# control_board-M0_breakout.net
KiCad netlist of a schematic drawn in EAGLE
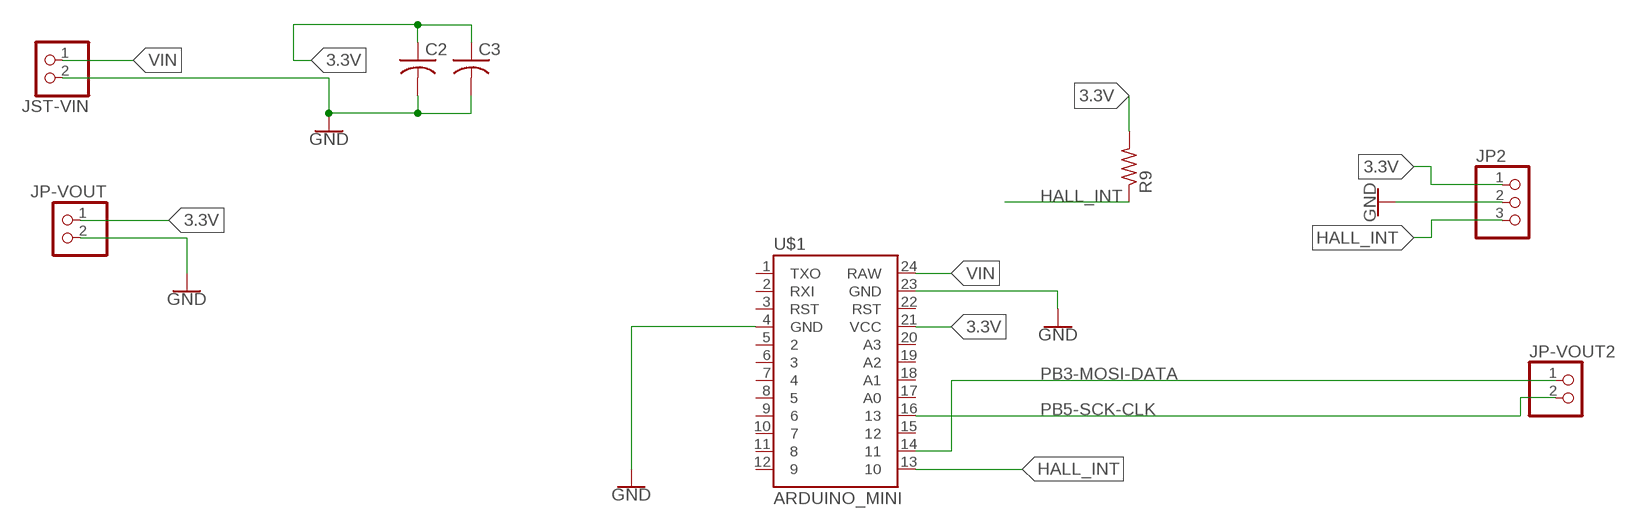
[diagram p0: schematic, sheet 1]

(export (version "E")
  (design (tool "Eeschema 10.0.6"))
  (components
    (comp (ref "C2")
      (value "C-US025-060X050")
      (footprint "eagle-import:C025-060X050")
      (libsource (lib "eagle-import") (part "C-US025-060X050"))
    )
    (comp (ref "C3")
      (value "C-US025-060X050")
      (footprint "eagle-import:C025-060X050")
      (libsource (lib "eagle-import") (part "C-US025-060X050"))
    )
    (comp (ref "JP-VOUT")
      (value "PINHD-1X2")
      (footprint "eagle-import:1X02")
      (libsource (lib "eagle-import") (part "PINHD-1X2"))
    )
    (comp (ref "JP-VOUT2")
      (value "PINHD-1X2")
      (footprint "eagle-import:1X02")
      (libsource (lib "eagle-import") (part "PINHD-1X2"))
    )
    (comp (ref "JP2")
      (value "PINHD-1X3")
      (footprint "eagle-import:1X03")
      (libsource (lib "eagle-import") (part "PINHD-1X3"))
    )
    (comp (ref "JST-VIN")
      (value "JST_2PIN-THM-RA")
      (footprint "eagle-import:JST-PH-2-THM-RA")
      (libsource (lib "eagle-import") (part "JST_2PIN-THM-RA"))
    )
    (comp (ref "R9")
      (value "R-US_0207/7")
      (footprint "eagle-import:0207_7")
      (libsource (lib "eagle-import") (part "R-US_0207/7"))
    )
    (comp (ref "U$1")
      (value "ARDUINO_MINI")
      (footprint "eagle-import:ARDUINO_MINI")
      (libsource (lib "eagle-import") (part "ARDUINO_MINI"))
    )
  )
  (nets
    (net (code "1") (name "/PB3-MOSI-DATA") (class "Default")
      (node (ref "JP-VOUT2") (pin "1") (pinfunction "1_1") (pintype "passive"))
      (node (ref "U$1") (pin "14") (pinfunction "11_14") (pintype "bidirectional"))
    )
    (net (code "2") (name "/PB5-SCK-CLK") (class "Default")
      (node (ref "JP-VOUT2") (pin "2") (pinfunction "2_2") (pintype "passive"))
      (node (ref "U$1") (pin "16") (pinfunction "13_16") (pintype "bidirectional"))
    )
    (net (code "3") (name "3.3V") (class "Default")
      (node (ref "C2") (pin "1") (pinfunction "1_1") (pintype "passive"))
      (node (ref "C3") (pin "1") (pinfunction "1_1") (pintype "passive"))
      (node (ref "JP-VOUT") (pin "1") (pinfunction "1_1") (pintype "passive"))
      (node (ref "JP2") (pin "1") (pinfunction "1_1") (pintype "passive"))
      (node (ref "R9") (pin "2") (pinfunction "2_2") (pintype "passive"))
      (node (ref "U$1") (pin "21") (pinfunction "VCC_21") (pintype "bidirectional"))
    )
    (net (code "4") (name "GND") (class "Default")
      (node (ref "C2") (pin "2") (pinfunction "2_2") (pintype "passive"))
      (node (ref "C3") (pin "2") (pinfunction "2_2") (pintype "passive"))
      (node (ref "JP-VOUT") (pin "2") (pinfunction "2_2") (pintype "passive"))
      (node (ref "JP2") (pin "2") (pinfunction "2_2") (pintype "passive"))
      (node (ref "JST-VIN") (pin "2") (pinfunction "1_2") (pintype "passive"))
      (node (ref "U$1") (pin "23") (pinfunction "GND_23") (pintype "bidirectional"))
      (node (ref "U$1") (pin "4") (pinfunction "GND_4") (pintype "bidirectional"))
    )
    (net (code "5") (name "HALL_INT") (class "Default")
      (node (ref "JP2") (pin "3") (pinfunction "3_3") (pintype "passive"))
      (node (ref "R9") (pin "1") (pinfunction "1_1") (pintype "passive"))
      (node (ref "U$1") (pin "13") (pinfunction "10_13") (pintype "bidirectional"))
    )
    (net (code "6") (name "VIN") (class "Default")
      (node (ref "JST-VIN") (pin "1") (pinfunction "2_1") (pintype "passive"))
      (node (ref "U$1") (pin "24") (pinfunction "RAW_24") (pintype "bidirectional"))
    )
    (net (code "7") (name "unconnected-(U$1-2-Pad5)") (class "Default")
      (node (ref "U$1") (pin "5") (pinfunction "2_5") (pintype "bidirectional"))
    )
    (net (code "8") (name "unconnected-(U$1-3-Pad6)") (class "Default")
      (node (ref "U$1") (pin "6") (pinfunction "3_6") (pintype "bidirectional"))
    )
    (net (code "9") (name "unconnected-(U$1-4-Pad7)") (class "Default")
      (node (ref "U$1") (pin "7") (pinfunction "4_7") (pintype "bidirectional"))
    )
    (net (code "10") (name "unconnected-(U$1-5-Pad8)") (class "Default")
      (node (ref "U$1") (pin "8") (pinfunction "5_8") (pintype "bidirectional"))
    )
    (net (code "11") (name "unconnected-(U$1-6-Pad9)") (class "Default")
      (node (ref "U$1") (pin "9") (pinfunction "6_9") (pintype "bidirectional"))
    )
    (net (code "12") (name "unconnected-(U$1-7-Pad10)") (class "Default")
      (node (ref "U$1") (pin "10") (pinfunction "7_10") (pintype "bidirectional"))
    )
    (net (code "13") (name "unconnected-(U$1-8-Pad11)") (class "Default")
      (node (ref "U$1") (pin "11") (pinfunction "8_11") (pintype "bidirectional"))
    )
    (net (code "14") (name "unconnected-(U$1-9-Pad12)") (class "Default")
      (node (ref "U$1") (pin "12") (pinfunction "9_12") (pintype "bidirectional"))
    )
    (net (code "15") (name "unconnected-(U$1-12-Pad15)") (class "Default")
      (node (ref "U$1") (pin "15") (pinfunction "12_15") (pintype "bidirectional"))
    )
    (net (code "16") (name "unconnected-(U$1-A0-Pad17)") (class "Default")
      (node (ref "U$1") (pin "17") (pinfunction "A0_17") (pintype "bidirectional"))
    )
    (net (code "17") (name "unconnected-(U$1-A1-Pad18)") (class "Default")
      (node (ref "U$1") (pin "18") (pinfunction "A1_18") (pintype "bidirectional"))
    )
    (net (code "18") (name "unconnected-(U$1-A2-Pad19)") (class "Default")
      (node (ref "U$1") (pin "19") (pinfunction "A2_19") (pintype "bidirectional"))
    )
    (net (code "19") (name "unconnected-(U$1-A3-Pad20)") (class "Default")
      (node (ref "U$1") (pin "20") (pinfunction "A3_20") (pintype "bidirectional"))
    )
    (net (code "20") (name "unconnected-(U$1-RST-Pad3)") (class "Default")
      (node (ref "U$1") (pin "3") (pinfunction "RST_3") (pintype "bidirectional"))
    )
    (net (code "21") (name "unconnected-(U$1-RST-Pad22)") (class "Default")
      (node (ref "U$1") (pin "22") (pinfunction "RST_22") (pintype "bidirectional"))
    )
    (net (code "22") (name "unconnected-(U$1-RXI-Pad2)") (class "Default")
      (node (ref "U$1") (pin "2") (pinfunction "RXI_2") (pintype "bidirectional"))
    )
    (net (code "23") (name "unconnected-(U$1-TXO-Pad1)") (class "Default")
      (node (ref "U$1") (pin "1") (pinfunction "TXO_1") (pintype "bidirectional"))
    )
  )
)
